# Input_Conditioner.net
KiCad netlist of a schematic drawn in Altium Designer
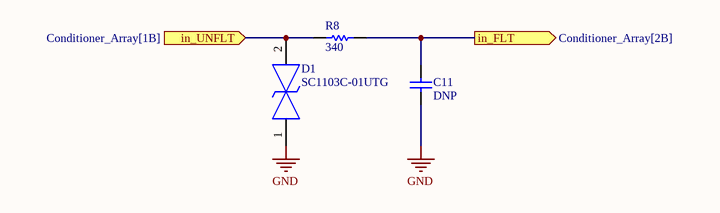
[diagram p0: Input_Conditioner.SchDoc]

(export (version "E")
  (design (tool "Eeschema 10.0.6"))
  (components
    (comp (ref "C11")
      (value "DNP")
      (footprint "FP-RC1608-IPC_A")
      (description "Capacitor")
      (libsource (lib "Simulation Generic Components") (part "Capacitor"))
    )
    (comp (ref "D1")
      (value "SC1103C-01UTG")
      (footprint "SamacSys:SC1103C01UTG")
      (description "TVS Diode (Bi-directional)")
      (fields (field (name "MOUSER PART NUMBER") "576-SC1103C-01UTG"))
      (libsource (lib "*") (part "SC1103C-01UTG"))
    )
    (comp (ref "R8")
      (value "340")
      (footprint "RESC1608X55X25LL10T15")
      (fields (field (name "PART NUMBER") "RC0603FR-07340RL") (field (name "MANUFACTURER") "Yageo"))
      (libsource (lib "Altium Content Vault") (part "RES"))
    )
  )
  (nets
    (net (code "1") (name "/in_FLT") (class "Default")
      (node (ref "C11") (pin "1") (pinfunction "1_1") (pintype "passive"))
      (node (ref "R8") (pin "2") (pinfunction "2_2") (pintype "passive"))
    )
    (net (code "2") (name "/in_UNFLT") (class "Default")
      (node (ref "D1") (pin "2") (pinfunction "2_2") (pintype "passive"))
      (node (ref "R8") (pin "1") (pinfunction "1_1") (pintype "passive"))
    )
    (net (code "3") (name "GND") (class "Default")
      (node (ref "C11") (pin "2") (pinfunction "2_2") (pintype "passive"))
      (node (ref "D1") (pin "1") (pinfunction "1_1") (pintype "passive"))
    )
  )
)
